# potenciostato_last.net
KiCad netlist of a schematic drawn in EAGLE
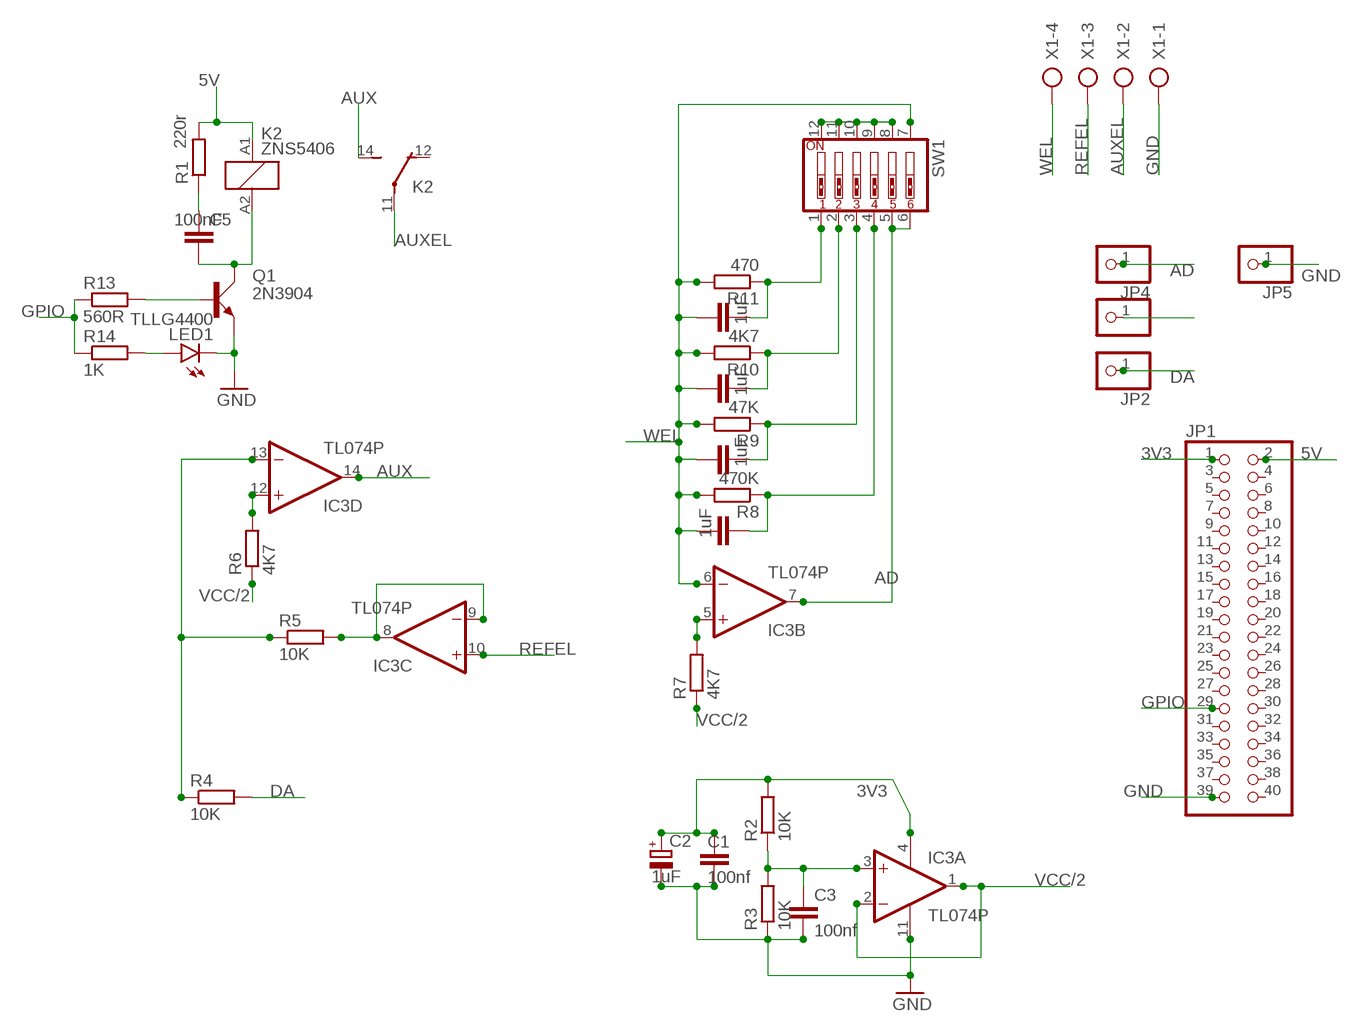
[diagram p0: schematic, sheet 1]

(export (version "E")
  (design (tool "Eeschema 10.0.6"))
  (components
    (comp (ref "C1")
      (value "100nf")
      (footprint "eagle-import:C050-035X075")
      (libsource (lib "eagle-import") (part "C-EU050-035X075"))
    )
    (comp (ref "C2")
      (value "1uF")
      (footprint "eagle-import:E2,5-5")
      (libsource (lib "eagle-import") (part "CPOL-EUE2.5-5"))
    )
    (comp (ref "C3")
      (value "100nf")
      (footprint "eagle-import:C050-035X075")
      (libsource (lib "eagle-import") (part "C-EU050-035X075"))
    )
    (comp (ref "C4")
      (value "1uF")
      (footprint "eagle-import:C050-035X075")
      (libsource (lib "eagle-import") (part "C-EU050-035X075"))
    )
    (comp (ref "C5")
      (value "100nF")
      (footprint "eagle-import:C050-035X075")
      (libsource (lib "eagle-import") (part "C-EU050-035X075"))
    )
    (comp (ref "C6")
      (value "1uF")
      (footprint "eagle-import:C050-035X075")
      (libsource (lib "eagle-import") (part "C-EU050-035X075"))
    )
    (comp (ref "C7")
      (value "1uF")
      (footprint "eagle-import:C050-035X075")
      (libsource (lib "eagle-import") (part "C-EU050-035X075"))
    )
    (comp (ref "C8")
      (value "1uF")
      (footprint "eagle-import:C050-035X075")
      (libsource (lib "eagle-import") (part "C-EU050-035X075"))
    )
    (comp (ref "IC3")
      (value "TL074P")
      (footprint "eagle-import:DIL14")
      (libsource (lib "eagle-import") (part "TL074P"))
    )
    (comp (ref "JP1")
      (value "PINHD-2X20/90")
      (footprint "eagle-import:2X20_90")
      (libsource (lib "eagle-import") (part "PINHD-2X20/90"))
    )
    (comp (ref "JP2")
      (value "PINHD-1X1")
      (footprint "eagle-import:1X01")
      (libsource (lib "eagle-import") (part "PINHD-1X1"))
    )
    (comp (ref "JP3")
      (value "PINHD-1X1")
      (footprint "eagle-import:1X01")
      (libsource (lib "eagle-import") (part "PINHD-1X1"))
    )
    (comp (ref "JP4")
      (value "PINHD-1X1")
      (footprint "eagle-import:1X01")
      (libsource (lib "eagle-import") (part "PINHD-1X1"))
    )
    (comp (ref "JP5")
      (value "PINHD-1X1")
      (footprint "eagle-import:1X01")
      (libsource (lib "eagle-import") (part "PINHD-1X1"))
    )
    (comp (ref "K2")
      (value "ZNS5406")
      (footprint "eagle-import:ZN5")
      (libsource (lib "eagle-import") (part "ZNS5406"))
    )
    (comp (ref "LED1")
      (value "TLLG4400")
      (footprint "eagle-import:LED3MM")
      (fields (field (name "MF") "VISHAY SEMICONDUCTOR"))
      (libsource (lib "eagle-import") (part "TLLG4400"))
    )
    (comp (ref "Q1")
      (value "2N3904")
      (footprint "eagle-import:TO92D")
      (libsource (lib "eagle-import") (part "2N3904"))
    )
    (comp (ref "R1")
      (value "220r")
      (footprint "eagle-import:0207_7")
      (libsource (lib "eagle-import") (part "R-EU_0207/7"))
    )
    (comp (ref "R2")
      (value "10K")
      (footprint "eagle-import:0207_7")
      (libsource (lib "eagle-import") (part "R-EU_0207/7"))
    )
    (comp (ref "R3")
      (value "10K")
      (footprint "eagle-import:0207_7")
      (libsource (lib "eagle-import") (part "R-EU_0207/7"))
    )
    (comp (ref "R4")
      (value "10K")
      (footprint "eagle-import:0207_7")
      (libsource (lib "eagle-import") (part "R-EU_0207/7"))
    )
    (comp (ref "R5")
      (value "10K")
      (footprint "eagle-import:0207_7")
      (libsource (lib "eagle-import") (part "R-EU_0207/7"))
    )
    (comp (ref "R6")
      (value "4K7")
      (footprint "eagle-import:0207_7")
      (libsource (lib "eagle-import") (part "R-EU_0207/7"))
    )
    (comp (ref "R7")
      (value "4K7")
      (footprint "eagle-import:0207_7")
      (libsource (lib "eagle-import") (part "R-EU_0207/7"))
    )
    (comp (ref "R8")
      (value "470K")
      (footprint "eagle-import:0207_7")
      (libsource (lib "eagle-import") (part "R-EU_0207/7"))
    )
    (comp (ref "R9")
      (value "47K")
      (footprint "eagle-import:0207_7")
      (libsource (lib "eagle-import") (part "R-EU_0207/7"))
    )
    (comp (ref "R10")
      (value "4K7")
      (footprint "eagle-import:0207_7")
      (libsource (lib "eagle-import") (part "R-EU_0207/7"))
    )
    (comp (ref "R11")
      (value "470")
      (footprint "eagle-import:0207_7")
      (libsource (lib "eagle-import") (part "R-EU_0207/7"))
    )
    (comp (ref "R13")
      (value "560R")
      (footprint "eagle-import:0207_7")
      (libsource (lib "eagle-import") (part "R-EU_0207/7"))
    )
    (comp (ref "R14")
      (value "1K")
      (footprint "eagle-import:0207_7")
      (libsource (lib "eagle-import") (part "R-EU_0207/7"))
    )
    (comp (ref "SW1")
      (value "SW_DIP-6")
      (footprint "eagle-import:EDG-06")
      (libsource (lib "eagle-import") (part "SW_DIP-6"))
    )
    (comp (ref "X1")
      (value "AK500/4")
      (footprint "eagle-import:AK500_4")
      (libsource (lib "eagle-import") (part "AK500/4"))
    )
  )
  (nets
    (net (code "1") (name "/3V3") (class "Default")
      (node (ref "C1") (pin "1") (pinfunction "1_1") (pintype "passive"))
      (node (ref "C2") (pin "+") (pinfunction "+_+") (pintype "passive"))
      (node (ref "IC3") (pin "4") (pinfunction "V+_4") (pintype "power_in"))
      (node (ref "JP1") (pin "1") (pinfunction "1_1") (pintype "passive"))
      (node (ref "R2") (pin "2") (pinfunction "2_2") (pintype "passive"))
    )
    (net (code "2") (name "/5V") (class "Default")
      (node (ref "JP1") (pin "2") (pinfunction "2_2") (pintype "passive"))
      (node (ref "K2") (pin "A1") (pinfunction "1_A1") (pintype "passive"))
      (node (ref "R1") (pin "2") (pinfunction "2_2") (pintype "passive"))
    )
    (net (code "3") (name "/AD") (class "Default")
      (node (ref "IC3") (pin "7") (pinfunction "OUT_7") (pintype "output"))
      (node (ref "JP4") (pin "1") (pinfunction "1_1") (pintype "passive"))
      (node (ref "SW1") (pin "5") (pinfunction "5_5") (pintype "passive"))
      (node (ref "SW1") (pin "6") (pinfunction "6_6") (pintype "passive"))
    )
    (net (code "4") (name "/AUX") (class "Default")
      (node (ref "IC3") (pin "14") (pinfunction "OUT_14") (pintype "output"))
      (node (ref "K2") (pin "14") (pinfunction "S_14") (pintype "passive"))
    )
    (net (code "5") (name "/AUXEL") (class "Default")
      (node (ref "K2") (pin "11") (pinfunction "P_11") (pintype "passive"))
      (node (ref "X1") (pin "2") (pinfunction "KL_2") (pintype "passive"))
    )
    (net (code "6") (name "/DA") (class "Default")
      (node (ref "JP2") (pin "1") (pinfunction "1_1") (pintype "passive"))
      (node (ref "R4") (pin "2") (pinfunction "2_2") (pintype "passive"))
    )
    (net (code "7") (name "/GPIO") (class "Default")
      (node (ref "JP1") (pin "29") (pinfunction "29_29") (pintype "passive"))
      (node (ref "R13") (pin "1") (pinfunction "1_1") (pintype "passive"))
      (node (ref "R14") (pin "1") (pinfunction "1_1") (pintype "passive"))
    )
    (net (code "8") (name "/REFEL") (class "Default")
      (node (ref "IC3") (pin "10") (pinfunction "+IN_10") (pintype "input"))
      (node (ref "X1") (pin "3") (pinfunction "KL_3") (pintype "passive"))
    )
    (net (code "9") (name "/VCC{slash}2") (class "Default")
      (node (ref "IC3") (pin "1") (pinfunction "OUT_1") (pintype "output"))
      (node (ref "IC3") (pin "2") (pinfunction "-IN_2") (pintype "input"))
      (node (ref "R6") (pin "1") (pinfunction "1_1") (pintype "passive"))
      (node (ref "R7") (pin "1") (pinfunction "1_1") (pintype "passive"))
    )
    (net (code "10") (name "/WEL") (class "Default")
      (node (ref "C4") (pin "1") (pinfunction "1_1") (pintype "passive"))
      (node (ref "C6") (pin "1") (pinfunction "1_1") (pintype "passive"))
      (node (ref "C7") (pin "1") (pinfunction "1_1") (pintype "passive"))
      (node (ref "C8") (pin "1") (pinfunction "1_1") (pintype "passive"))
      (node (ref "IC3") (pin "6") (pinfunction "-IN_6") (pintype "input"))
      (node (ref "R10") (pin "2") (pinfunction "2_2") (pintype "passive"))
      (node (ref "R11") (pin "2") (pinfunction "2_2") (pintype "passive"))
      (node (ref "R8") (pin "2") (pinfunction "2_2") (pintype "passive"))
      (node (ref "R9") (pin "2") (pinfunction "2_2") (pintype "passive"))
      (node (ref "SW1") (pin "7") (pinfunction "7_7") (pintype "passive"))
      (node (ref "X1") (pin "4") (pinfunction "KL_4") (pintype "passive"))
    )
    (net (code "11") (name "GND") (class "Default")
      (node (ref "C1") (pin "2") (pinfunction "2_2") (pintype "passive"))
      (node (ref "C2") (pin "-") (pinfunction "-_-") (pintype "passive"))
      (node (ref "C3") (pin "2") (pinfunction "2_2") (pintype "passive"))
      (node (ref "IC3") (pin "11") (pinfunction "V-_11") (pintype "power_in"))
      (node (ref "JP1") (pin "39") (pinfunction "39_39") (pintype "passive"))
      (node (ref "JP5") (pin "1") (pinfunction "1_1") (pintype "passive"))
      (node (ref "LED1") (pin "K") (pinfunction "C_K") (pintype "passive"))
      (node (ref "Q1") (pin "E") (pinfunction "E_E") (pintype "passive"))
      (node (ref "R3") (pin "1") (pinfunction "1_1") (pintype "passive"))
      (node (ref "X1") (pin "1") (pinfunction "KL_1") (pintype "passive"))
    )
    (net (code "12") (name "Net-(C4-Pad2)") (class "Default")
      (node (ref "C4") (pin "2") (pinfunction "2_2") (pintype "passive"))
      (node (ref "R8") (pin "1") (pinfunction "1_1") (pintype "passive"))
      (node (ref "SW1") (pin "4") (pinfunction "4_4") (pintype "passive"))
    )
    (net (code "13") (name "Net-(C5-Pad1)") (class "Default")
      (node (ref "C5") (pin "1") (pinfunction "1_1") (pintype "passive"))
      (node (ref "R1") (pin "1") (pinfunction "1_1") (pintype "passive"))
    )
    (net (code "14") (name "Net-(C6-Pad2)") (class "Default")
      (node (ref "C6") (pin "2") (pinfunction "2_2") (pintype "passive"))
      (node (ref "R11") (pin "1") (pinfunction "1_1") (pintype "passive"))
      (node (ref "SW1") (pin "1") (pinfunction "1_1") (pintype "passive"))
    )
    (net (code "15") (name "Net-(C7-Pad2)") (class "Default")
      (node (ref "C7") (pin "2") (pinfunction "2_2") (pintype "passive"))
      (node (ref "R10") (pin "1") (pinfunction "1_1") (pintype "passive"))
      (node (ref "SW1") (pin "2") (pinfunction "2_2") (pintype "passive"))
    )
    (net (code "16") (name "Net-(C8-Pad2)") (class "Default")
      (node (ref "C8") (pin "2") (pinfunction "2_2") (pintype "passive"))
      (node (ref "R9") (pin "1") (pinfunction "1_1") (pintype "passive"))
      (node (ref "SW1") (pin "3") (pinfunction "3_3") (pintype "passive"))
    )
    (net (code "17") (name "Net-(IC3A-+IN)") (class "Default")
      (node (ref "C3") (pin "1") (pinfunction "1_1") (pintype "passive"))
      (node (ref "IC3") (pin "3") (pinfunction "+IN_3") (pintype "input"))
      (node (ref "R2") (pin "1") (pinfunction "1_1") (pintype "passive"))
      (node (ref "R3") (pin "2") (pinfunction "2_2") (pintype "passive"))
    )
    (net (code "18") (name "Net-(IC3B-+IN)") (class "Default")
      (node (ref "IC3") (pin "5") (pinfunction "+IN_5") (pintype "input"))
      (node (ref "R7") (pin "2") (pinfunction "2_2") (pintype "passive"))
    )
    (net (code "19") (name "Net-(IC3C--IN)") (class "Default")
      (node (ref "IC3") (pin "8") (pinfunction "OUT_8") (pintype "output"))
      (node (ref "IC3") (pin "9") (pinfunction "-IN_9") (pintype "input"))
      (node (ref "R5") (pin "2") (pinfunction "2_2") (pintype "passive"))
    )
    (net (code "20") (name "Net-(IC3D-+IN)") (class "Default")
      (node (ref "IC3") (pin "12") (pinfunction "+IN_12") (pintype "input"))
      (node (ref "R6") (pin "2") (pinfunction "2_2") (pintype "passive"))
    )
    (net (code "21") (name "Net-(IC3D--IN)") (class "Default")
      (node (ref "IC3") (pin "13") (pinfunction "-IN_13") (pintype "input"))
      (node (ref "R4") (pin "1") (pinfunction "1_1") (pintype "passive"))
      (node (ref "R5") (pin "1") (pinfunction "1_1") (pintype "passive"))
    )
    (net (code "22") (name "Net-(K2A-2)") (class "Default")
      (node (ref "C5") (pin "2") (pinfunction "2_2") (pintype "passive"))
      (node (ref "K2") (pin "A2") (pinfunction "2_A2") (pintype "passive"))
      (node (ref "Q1") (pin "C") (pinfunction "C_C") (pintype "passive"))
    )
    (net (code "23") (name "Net-(LED1-PadA)") (class "Default")
      (node (ref "LED1") (pin "A") (pinfunction "A_A") (pintype "passive"))
      (node (ref "R14") (pin "2") (pinfunction "2_2") (pintype "passive"))
    )
    (net (code "24") (name "Net-(Q1-PadB)") (class "Default")
      (node (ref "Q1") (pin "B") (pinfunction "B_B") (pintype "passive"))
      (node (ref "R13") (pin "2") (pinfunction "2_2") (pintype "passive"))
    )
    (net (code "25") (name "Net-(SW1-Pad10)") (class "Default")
      (node (ref "SW1") (pin "10") (pinfunction "10_10") (pintype "passive"))
      (node (ref "SW1") (pin "11") (pinfunction "11_11") (pintype "passive"))
      (node (ref "SW1") (pin "12") (pinfunction "12_12") (pintype "passive"))
      (node (ref "SW1") (pin "8") (pinfunction "8_8") (pintype "passive"))
      (node (ref "SW1") (pin "9") (pinfunction "9_9") (pintype "passive"))
    )
    (net (code "26") (name "unconnected-(JP1-Pad3)") (class "Default")
      (node (ref "JP1") (pin "3") (pinfunction "3_3") (pintype "passive"))
    )
    (net (code "27") (name "unconnected-(JP1-Pad4)") (class "Default")
      (node (ref "JP1") (pin "4") (pinfunction "4_4") (pintype "passive"))
    )
    (net (code "28") (name "unconnected-(JP1-Pad5)") (class "Default")
      (node (ref "JP1") (pin "5") (pinfunction "5_5") (pintype "passive"))
    )
    (net (code "29") (name "unconnected-(JP1-Pad6)") (class "Default")
      (node (ref "JP1") (pin "6") (pinfunction "6_6") (pintype "passive"))
    )
    (net (code "30") (name "unconnected-(JP1-Pad7)") (class "Default")
      (node (ref "JP1") (pin "7") (pinfunction "7_7") (pintype "passive"))
    )
    (net (code "31") (name "unconnected-(JP1-Pad8)") (class "Default")
      (node (ref "JP1") (pin "8") (pinfunction "8_8") (pintype "passive"))
    )
    (net (code "32") (name "unconnected-(JP1-Pad9)") (class "Default")
      (node (ref "JP1") (pin "9") (pinfunction "9_9") (pintype "passive"))
    )
    (net (code "33") (name "unconnected-(JP1-Pad10)") (class "Default")
      (node (ref "JP1") (pin "10") (pinfunction "10_10") (pintype "passive"))
    )
    (net (code "34") (name "unconnected-(JP1-Pad11)") (class "Default")
      (node (ref "JP1") (pin "11") (pinfunction "11_11") (pintype "passive"))
    )
    (net (code "35") (name "unconnected-(JP1-Pad12)") (class "Default")
      (node (ref "JP1") (pin "12") (pinfunction "12_12") (pintype "passive"))
    )
    (net (code "36") (name "unconnected-(JP1-Pad13)") (class "Default")
      (node (ref "JP1") (pin "13") (pinfunction "13_13") (pintype "passive"))
    )
    (net (code "37") (name "unconnected-(JP1-Pad14)") (class "Default")
      (node (ref "JP1") (pin "14") (pinfunction "14_14") (pintype "passive"))
    )
    (net (code "38") (name "unconnected-(JP1-Pad15)") (class "Default")
      (node (ref "JP1") (pin "15") (pinfunction "15_15") (pintype "passive"))
    )
    (net (code "39") (name "unconnected-(JP1-Pad16)") (class "Default")
      (node (ref "JP1") (pin "16") (pinfunction "16_16") (pintype "passive"))
    )
    (net (code "40") (name "unconnected-(JP1-Pad17)") (class "Default")
      (node (ref "JP1") (pin "17") (pinfunction "17_17") (pintype "passive"))
    )
    (net (code "41") (name "unconnected-(JP1-Pad18)") (class "Default")
      (node (ref "JP1") (pin "18") (pinfunction "18_18") (pintype "passive"))
    )
    (net (code "42") (name "unconnected-(JP1-Pad19)") (class "Default")
      (node (ref "JP1") (pin "19") (pinfunction "19_19") (pintype "passive"))
    )
    (net (code "43") (name "unconnected-(JP1-Pad20)") (class "Default")
      (node (ref "JP1") (pin "20") (pinfunction "20_20") (pintype "passive"))
    )
    (net (code "44") (name "unconnected-(JP1-Pad21)") (class "Default")
      (node (ref "JP1") (pin "21") (pinfunction "21_21") (pintype "passive"))
    )
    (net (code "45") (name "unconnected-(JP1-Pad22)") (class "Default")
      (node (ref "JP1") (pin "22") (pinfunction "22_22") (pintype "passive"))
    )
    (net (code "46") (name "unconnected-(JP1-Pad23)") (class "Default")
      (node (ref "JP1") (pin "23") (pinfunction "23_23") (pintype "passive"))
    )
    (net (code "47") (name "unconnected-(JP1-Pad24)") (class "Default")
      (node (ref "JP1") (pin "24") (pinfunction "24_24") (pintype "passive"))
    )
    (net (code "48") (name "unconnected-(JP1-Pad25)") (class "Default")
      (node (ref "JP1") (pin "25") (pinfunction "25_25") (pintype "passive"))
    )
    (net (code "49") (name "unconnected-(JP1-Pad26)") (class "Default")
      (node (ref "JP1") (pin "26") (pinfunction "26_26") (pintype "passive"))
    )
    (net (code "50") (name "unconnected-(JP1-Pad27)") (class "Default")
      (node (ref "JP1") (pin "27") (pinfunction "27_27") (pintype "passive"))
    )
    (net (code "51") (name "unconnected-(JP1-Pad28)") (class "Default")
      (node (ref "JP1") (pin "28") (pinfunction "28_28") (pintype "passive"))
    )
    (net (code "52") (name "unconnected-(JP1-Pad30)") (class "Default")
      (node (ref "JP1") (pin "30") (pinfunction "30_30") (pintype "passive"))
    )
    (net (code "53") (name "unconnected-(JP1-Pad31)") (class "Default")
      (node (ref "JP1") (pin "31") (pinfunction "31_31") (pintype "passive"))
    )
    (net (code "54") (name "unconnected-(JP1-Pad32)") (class "Default")
      (node (ref "JP1") (pin "32") (pinfunction "32_32") (pintype "passive"))
    )
    (net (code "55") (name "unconnected-(JP1-Pad33)") (class "Default")
      (node (ref "JP1") (pin "33") (pinfunction "33_33") (pintype "passive"))
    )
    (net (code "56") (name "unconnected-(JP1-Pad34)") (class "Default")
      (node (ref "JP1") (pin "34") (pinfunction "34_34") (pintype "passive"))
    )
    (net (code "57") (name "unconnected-(JP1-Pad35)") (class "Default")
      (node (ref "JP1") (pin "35") (pinfunction "35_35") (pintype "passive"))
    )
    (net (code "58") (name "unconnected-(JP1-Pad36)") (class "Default")
      (node (ref "JP1") (pin "36") (pinfunction "36_36") (pintype "passive"))
    )
    (net (code "59") (name "unconnected-(JP1-Pad37)") (class "Default")
      (node (ref "JP1") (pin "37") (pinfunction "37_37") (pintype "passive"))
    )
    (net (code "60") (name "unconnected-(JP1-Pad38)") (class "Default")
      (node (ref "JP1") (pin "38") (pinfunction "38_38") (pintype "passive"))
    )
    (net (code "61") (name "unconnected-(JP1-Pad40)") (class "Default")
      (node (ref "JP1") (pin "40") (pinfunction "40_40") (pintype "passive"))
    )
    (net (code "62") (name "unconnected-(JP3-Pad1)") (class "Default")
      (node (ref "JP3") (pin "1") (pinfunction "1_1") (pintype "passive"))
    )
    (net (code "63") (name "unconnected-(K2B-O-Pad12)") (class "Default")
      (node (ref "K2") (pin "12") (pinfunction "O_12") (pintype "passive"))
    )
  )
)
